# servo_1.net
KiCad netlist of a schematic drawn in EAGLE
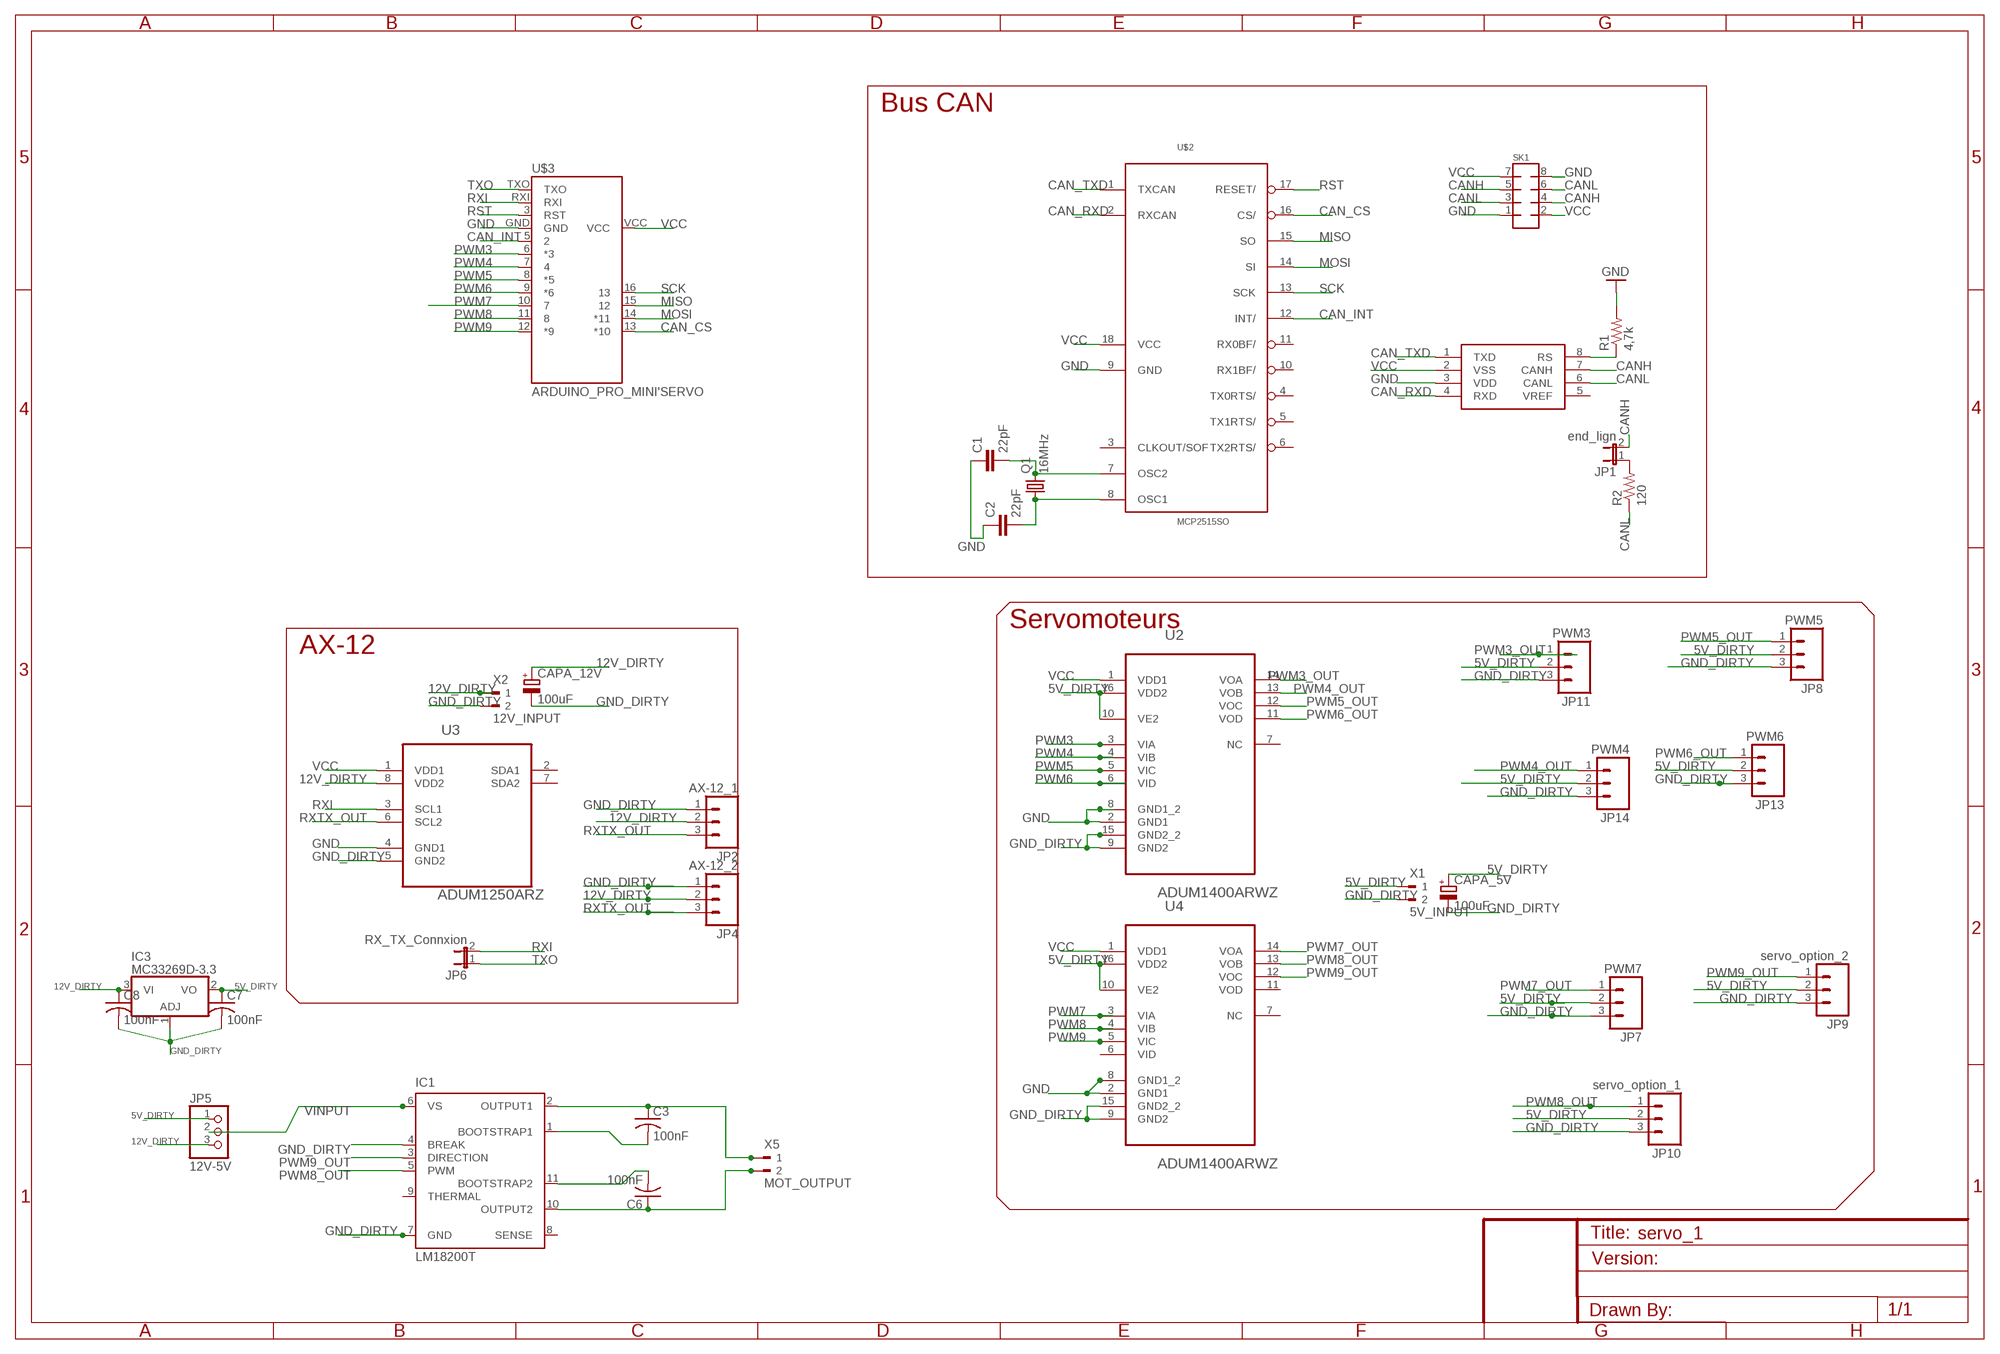
[diagram p0: schematic, sheet 1]

(export (version "E")
  (design (tool "Eeschema 10.0.6"))
  (components
    (comp (ref "C1")
      (value "22pF")
      (footprint "eagle-import:0805")
      (libsource (lib "eagle-import") (part "CAP0805"))
    )
    (comp (ref "C2")
      (value "22pF")
      (footprint "eagle-import:0805")
      (libsource (lib "eagle-import") (part "CAP0805"))
    )
    (comp (ref "C3")
      (value "100nF")
      (footprint "eagle-import:C0805")
      (libsource (lib "eagle-import") (part "C-USC0805"))
    )
    (comp (ref "C6")
      (value "100nF")
      (footprint "eagle-import:C0805")
      (libsource (lib "eagle-import") (part "C-USC0805"))
    )
    (comp (ref "C7")
      (value "100nF")
      (footprint "eagle-import:C0805")
      (libsource (lib "eagle-import") (part "C-USC0805"))
    )
    (comp (ref "C8")
      (value "100nF")
      (footprint "eagle-import:C0805")
      (libsource (lib "eagle-import") (part "C-USC0805"))
    )
    (comp (ref "CAPA_5V")
      (value "100uF")
      (footprint "eagle-import:E5-8,5")
      (libsource (lib "eagle-import") (part "CPOL-EUE5-8.5"))
    )
    (comp (ref "CAPA_12V")
      (value "100uF")
      (footprint "eagle-import:E5-8,5")
      (libsource (lib "eagle-import") (part "CPOL-EUE5-8.5"))
    )
    (comp (ref "IC1")
      (value "LM18200T")
      (footprint "eagle-import:TO-220-11")
      (libsource (lib "eagle-import") (part "LM18200T"))
    )
    (comp (ref "IC3")
      (value "MC33269D-3.3")
      (footprint "eagle-import:DPACK")
      (libsource (lib "eagle-import") (part "MC33269?D-3.3"))
    )
    (comp (ref "JP1")
      (value "end_lign")
      (footprint "eagle-import:1X02")
      (libsource (lib "eagle-import") (part "JUMPER-2PTH"))
    )
    (comp (ref "JP2")
      (value "AX-12_1")
      (footprint "eagle-import:MOLEX-1X3")
      (libsource (lib "eagle-import") (part "M03POLAR"))
    )
    (comp (ref "JP4")
      (value "AX-12_2")
      (footprint "eagle-import:MOLEX-1X3")
      (libsource (lib "eagle-import") (part "M03POLAR"))
    )
    (comp (ref "JP5")
      (value "12V-5V")
      (footprint "eagle-import:1X03")
      (libsource (lib "eagle-import") (part "PINHD-1X3"))
    )
    (comp (ref "JP6")
      (value "RX_TX_Connxion")
      (footprint "eagle-import:1X02")
      (libsource (lib "eagle-import") (part "JUMPER-2PTH"))
    )
    (comp (ref "JP7")
      (value "PWM7")
      (footprint "eagle-import:1X03")
      (libsource (lib "eagle-import") (part "M03PTH"))
    )
    (comp (ref "JP8")
      (value "PWM5")
      (footprint "eagle-import:1X03")
      (libsource (lib "eagle-import") (part "M03PTH"))
    )
    (comp (ref "JP9")
      (value "servo_option_2")
      (footprint "eagle-import:1X03")
      (libsource (lib "eagle-import") (part "M03PTH"))
    )
    (comp (ref "JP10")
      (value "servo_option_1")
      (footprint "eagle-import:1X03")
      (libsource (lib "eagle-import") (part "M03PTH"))
    )
    (comp (ref "JP11")
      (value "PWM3")
      (footprint "eagle-import:1X03")
      (libsource (lib "eagle-import") (part "M03PTH"))
    )
    (comp (ref "JP13")
      (value "PWM6")
      (footprint "eagle-import:1X03")
      (libsource (lib "eagle-import") (part "M03PTH"))
    )
    (comp (ref "JP14")
      (value "PWM4")
      (footprint "eagle-import:1X03")
      (libsource (lib "eagle-import") (part "M03PTH"))
    )
    (comp (ref "Q1")
      (value "16MHz")
      (footprint "eagle-import:HC49_S")
      (libsource (lib "eagle-import") (part "CRYSTALHC49S"))
    )
    (comp (ref "R1")
      (value "4,7k")
      (footprint "eagle-import:0805")
      (libsource (lib "eagle-import") (part "RESISTOR0805-RES"))
    )
    (comp (ref "R2")
      (value "120")
      (footprint "eagle-import:0805")
      (libsource (lib "eagle-import") (part "RESISTOR0805-RES"))
    )
    (comp (ref "SK1")
      (value "MMATCH-8-PTH")
      (footprint "eagle-import:AMP-215079-8")
      (libsource (lib "eagle-import") (part "MMATCH-8-PTH"))
    )
    (comp (ref "U$2")
      (value "MCP2515SO")
      (footprint "eagle-import:SO18L")
      (libsource (lib "eagle-import") (part "MCP2515SO"))
    )
    (comp (ref "U$3")
      (value "ARDUINO_PRO_MINI'SERVO")
      (footprint "eagle-import:ARDUINO_PRO_MINI")
      (libsource (lib "eagle-import") (part "ARDUINO_PRO_MINI'SERVO"))
    )
    (comp (ref "U1")
      (value "MCP2551")
      (footprint "eagle-import:SO08")
      (libsource (lib "eagle-import") (part "MCP2551"))
    )
    (comp (ref "U2")
      (value "ADUM1400ARWZ")
      (footprint "eagle-import:SOIC127P1032X265-16N")
      (libsource (lib "eagle-import") (part "ADUM1400ARWZ"))
    )
    (comp (ref "U3")
      (value "ADUM1250ARZ")
      (footprint "eagle-import:SOIC127P600X175-8N")
      (libsource (lib "eagle-import") (part "ADUM1250ARZ"))
    )
    (comp (ref "U4")
      (value "ADUM1400ARWZ")
      (footprint "eagle-import:SOIC127P1032X265-16N")
      (libsource (lib "eagle-import") (part "ADUM1400ARWZ"))
    )
    (comp (ref "X1")
      (value "5V_INPUT")
      (footprint "eagle-import:90-2")
      (libsource (lib "eagle-import") (part "90-2"))
    )
    (comp (ref "X2")
      (value "12V_INPUT")
      (footprint "eagle-import:90-2")
      (libsource (lib "eagle-import") (part "90-2"))
    )
    (comp (ref "X5")
      (value "MOT_OUTPUT")
      (footprint "eagle-import:90-2")
      (libsource (lib "eagle-import") (part "90-2"))
    )
  )
  (nets
    (net (code "1") (name "/5V_DIRTY") (class "Default")
      (node (ref "C7") (pin "1") (pinfunction "1_1") (pintype "passive"))
      (node (ref "CAPA_5V") (pin "+") (pinfunction "+_+") (pintype "passive"))
      (node (ref "IC3") (pin "2") (pinfunction "VO_2") (pintype "passive"))
      (node (ref "JP10") (pin "2") (pinfunction "2_2") (pintype "passive"))
      (node (ref "JP11") (pin "2") (pinfunction "2_2") (pintype "passive"))
      (node (ref "JP13") (pin "2") (pinfunction "2_2") (pintype "passive"))
      (node (ref "JP14") (pin "2") (pinfunction "2_2") (pintype "passive"))
      (node (ref "JP5") (pin "1") (pinfunction "1_1") (pintype "passive"))
      (node (ref "JP7") (pin "2") (pinfunction "2_2") (pintype "passive"))
      (node (ref "JP8") (pin "2") (pinfunction "2_2") (pintype "passive"))
      (node (ref "JP9") (pin "2") (pinfunction "2_2") (pintype "passive"))
      (node (ref "U2") (pin "10") (pinfunction "VE2_10") (pintype "input"))
      (node (ref "U2") (pin "16") (pinfunction "VDD2_16") (pintype "power_in"))
      (node (ref "U4") (pin "10") (pinfunction "VE2_10") (pintype "input"))
      (node (ref "U4") (pin "16") (pinfunction "VDD2_16") (pintype "power_in"))
      (node (ref "X1") (pin "1") (pinfunction "1_1") (pintype "passive"))
    )
    (net (code "2") (name "/12V_DIRTY") (class "Default")
      (node (ref "C8") (pin "1") (pinfunction "1_1") (pintype "passive"))
      (node (ref "CAPA_12V") (pin "+") (pinfunction "+_+") (pintype "passive"))
      (node (ref "IC3") (pin "3") (pinfunction "VI_3") (pintype "input"))
      (node (ref "JP2") (pin "2") (pinfunction "2_2") (pintype "passive"))
      (node (ref "JP4") (pin "2") (pinfunction "2_2") (pintype "passive"))
      (node (ref "JP5") (pin "3") (pinfunction "3_3") (pintype "passive"))
      (node (ref "U3") (pin "8") (pinfunction "VDD2_8") (pintype "power_in"))
      (node (ref "X2") (pin "1") (pinfunction "1_1") (pintype "passive"))
    )
    (net (code "3") (name "/CANH") (class "Default")
      (node (ref "JP1") (pin "2") (pinfunction "2_2") (pintype "passive"))
      (node (ref "SK1") (pin "4") (pinfunction "4_4") (pintype "bidirectional"))
      (node (ref "SK1") (pin "5") (pinfunction "5_5") (pintype "bidirectional"))
      (node (ref "U1") (pin "7") (pinfunction "CANH_7") (pintype "bidirectional"))
    )
    (net (code "4") (name "/CANL") (class "Default")
      (node (ref "R2") (pin "1") (pinfunction "1_1") (pintype "passive"))
      (node (ref "SK1") (pin "3") (pinfunction "3_3") (pintype "bidirectional"))
      (node (ref "SK1") (pin "6") (pinfunction "6_6") (pintype "bidirectional"))
      (node (ref "U1") (pin "6") (pinfunction "CANL_6") (pintype "bidirectional"))
    )
    (net (code "5") (name "/CAN_CS") (class "Default")
      (node (ref "U$2") (pin "16") (pinfunction "CS/_16") (pintype "input"))
      (node (ref "U$3") (pin "13") (pinfunction "*10_13") (pintype "bidirectional"))
    )
    (net (code "6") (name "/CAN_INT") (class "Default")
      (node (ref "U$2") (pin "12") (pinfunction "INT/_12") (pintype "output"))
      (node (ref "U$3") (pin "5") (pinfunction "2_5") (pintype "bidirectional"))
    )
    (net (code "7") (name "/CAN_RXD") (class "Default")
      (node (ref "U$2") (pin "2") (pinfunction "RXCAN_2") (pintype "input"))
      (node (ref "U1") (pin "4") (pinfunction "RXD_4") (pintype "bidirectional"))
    )
    (net (code "8") (name "/CAN_TXD") (class "Default")
      (node (ref "U$2") (pin "1") (pinfunction "TXCAN_1") (pintype "output"))
      (node (ref "U1") (pin "1") (pinfunction "TXD_1") (pintype "bidirectional"))
    )
    (net (code "9") (name "/GND_DIRTY") (class "Default")
      (node (ref "C7") (pin "2") (pinfunction "2_2") (pintype "passive"))
      (node (ref "C8") (pin "2") (pinfunction "2_2") (pintype "passive"))
      (node (ref "CAPA_12V") (pin "-") (pinfunction "-_-") (pintype "passive"))
      (node (ref "CAPA_5V") (pin "-") (pinfunction "-_-") (pintype "passive"))
      (node (ref "IC1") (pin "4") (pinfunction "BREAK_4") (pintype "input"))
      (node (ref "IC1") (pin "7") (pinfunction "GND_7") (pintype "power_in"))
      (node (ref "IC3") (pin "1") (pinfunction "ADJ_1") (pintype "input"))
      (node (ref "JP10") (pin "3") (pinfunction "3_3") (pintype "passive"))
      (node (ref "JP11") (pin "3") (pinfunction "3_3") (pintype "passive"))
      (node (ref "JP13") (pin "3") (pinfunction "3_3") (pintype "passive"))
      (node (ref "JP14") (pin "3") (pinfunction "3_3") (pintype "passive"))
      (node (ref "JP2") (pin "1") (pinfunction "1_1") (pintype "passive"))
      (node (ref "JP4") (pin "1") (pinfunction "1_1") (pintype "passive"))
      (node (ref "JP7") (pin "3") (pinfunction "3_3") (pintype "passive"))
      (node (ref "JP8") (pin "3") (pinfunction "3_3") (pintype "passive"))
      (node (ref "JP9") (pin "3") (pinfunction "3_3") (pintype "passive"))
      (node (ref "U2") (pin "15") (pinfunction "GND2_2_15") (pintype "passive"))
      (node (ref "U2") (pin "9") (pinfunction "GND2_9") (pintype "passive"))
      (node (ref "U3") (pin "5") (pinfunction "GND2_5") (pintype "passive"))
      (node (ref "U4") (pin "15") (pinfunction "GND2_2_15") (pintype "passive"))
      (node (ref "U4") (pin "9") (pinfunction "GND2_9") (pintype "passive"))
      (node (ref "X1") (pin "2") (pinfunction "2_2") (pintype "passive"))
      (node (ref "X2") (pin "2") (pinfunction "2_2") (pintype "passive"))
    )
    (net (code "10") (name "/MISO") (class "Default")
      (node (ref "U$2") (pin "15") (pinfunction "SO_15") (pintype "output"))
      (node (ref "U$3") (pin "15") (pinfunction "12_15") (pintype "bidirectional"))
    )
    (net (code "11") (name "/MOSI") (class "Default")
      (node (ref "U$2") (pin "14") (pinfunction "SI_14") (pintype "input"))
      (node (ref "U$3") (pin "14") (pinfunction "*11_14") (pintype "bidirectional"))
    )
    (net (code "12") (name "/PWM3") (class "Default")
      (node (ref "U$3") (pin "6") (pinfunction "*3_6") (pintype "bidirectional"))
      (node (ref "U2") (pin "3") (pinfunction "VIA_3") (pintype "input"))
    )
    (net (code "13") (name "/PWM3_OUT") (class "Default")
      (node (ref "JP11") (pin "1") (pinfunction "1_1") (pintype "passive"))
      (node (ref "U2") (pin "14") (pinfunction "VOA_14") (pintype "output"))
    )
    (net (code "14") (name "/PWM4") (class "Default")
      (node (ref "U$3") (pin "7") (pinfunction "4_7") (pintype "bidirectional"))
      (node (ref "U2") (pin "4") (pinfunction "VIB_4") (pintype "input"))
    )
    (net (code "15") (name "/PWM4_OUT") (class "Default")
      (node (ref "JP14") (pin "1") (pinfunction "1_1") (pintype "passive"))
      (node (ref "U2") (pin "13") (pinfunction "VOB_13") (pintype "output"))
    )
    (net (code "16") (name "/PWM5") (class "Default")
      (node (ref "U$3") (pin "8") (pinfunction "*5_8") (pintype "bidirectional"))
      (node (ref "U2") (pin "5") (pinfunction "VIC_5") (pintype "input"))
    )
    (net (code "17") (name "/PWM5_OUT") (class "Default")
      (node (ref "JP8") (pin "1") (pinfunction "1_1") (pintype "passive"))
      (node (ref "U2") (pin "12") (pinfunction "VOC_12") (pintype "output"))
    )
    (net (code "18") (name "/PWM6") (class "Default")
      (node (ref "U$3") (pin "9") (pinfunction "*6_9") (pintype "bidirectional"))
      (node (ref "U2") (pin "6") (pinfunction "VID_6") (pintype "input"))
    )
    (net (code "19") (name "/PWM6_OUT") (class "Default")
      (node (ref "JP13") (pin "1") (pinfunction "1_1") (pintype "passive"))
      (node (ref "U2") (pin "11") (pinfunction "VOD_11") (pintype "output"))
    )
    (net (code "20") (name "/PWM7") (class "Default")
      (node (ref "U$3") (pin "10") (pinfunction "7_10") (pintype "bidirectional"))
      (node (ref "U4") (pin "3") (pinfunction "VIA_3") (pintype "input"))
    )
    (net (code "21") (name "/PWM7_OUT") (class "Default")
      (node (ref "JP7") (pin "1") (pinfunction "1_1") (pintype "passive"))
      (node (ref "U4") (pin "14") (pinfunction "VOA_14") (pintype "output"))
    )
    (net (code "22") (name "/PWM8") (class "Default")
      (node (ref "U$3") (pin "11") (pinfunction "8_11") (pintype "bidirectional"))
      (node (ref "U4") (pin "4") (pinfunction "VIB_4") (pintype "input"))
    )
    (net (code "23") (name "/PWM8_OUT") (class "Default")
      (node (ref "IC1") (pin "5") (pinfunction "PWM_5") (pintype "input"))
      (node (ref "JP10") (pin "1") (pinfunction "1_1") (pintype "passive"))
      (node (ref "U4") (pin "13") (pinfunction "VOB_13") (pintype "output"))
    )
    (net (code "24") (name "/PWM9") (class "Default")
      (node (ref "U$3") (pin "12") (pinfunction "*9_12") (pintype "bidirectional"))
      (node (ref "U4") (pin "5") (pinfunction "VIC_5") (pintype "input"))
    )
    (net (code "25") (name "/PWM9_OUT") (class "Default")
      (node (ref "IC1") (pin "3") (pinfunction "DIRECTION_3") (pintype "input"))
      (node (ref "JP9") (pin "1") (pinfunction "1_1") (pintype "passive"))
      (node (ref "U4") (pin "12") (pinfunction "VOC_12") (pintype "output"))
    )
    (net (code "26") (name "/RST") (class "Default")
      (node (ref "U$2") (pin "17") (pinfunction "RESET/_17") (pintype "input"))
      (node (ref "U$3") (pin "3") (pinfunction "RST_3") (pintype "bidirectional"))
    )
    (net (code "27") (name "/RXI") (class "Default")
      (node (ref "JP6") (pin "2") (pinfunction "2_2") (pintype "passive"))
      (node (ref "U$3") (pin "RXI") (pinfunction "RXI_RXI") (pintype "bidirectional"))
      (node (ref "U3") (pin "3") (pinfunction "SCL1_3") (pintype "input"))
    )
    (net (code "28") (name "/RXTX_OUT") (class "Default")
      (node (ref "JP2") (pin "3") (pinfunction "3_3") (pintype "passive"))
      (node (ref "JP4") (pin "3") (pinfunction "3_3") (pintype "passive"))
      (node (ref "U3") (pin "6") (pinfunction "SCL2_6") (pintype "input"))
    )
    (net (code "29") (name "/SCK") (class "Default")
      (node (ref "U$2") (pin "13") (pinfunction "SCK_13") (pintype "input"))
      (node (ref "U$3") (pin "16") (pinfunction "13_16") (pintype "bidirectional"))
    )
    (net (code "30") (name "/TXO") (class "Default")
      (node (ref "JP6") (pin "1") (pinfunction "1_1") (pintype "passive"))
      (node (ref "U$3") (pin "TXO") (pinfunction "TXO_TXO") (pintype "bidirectional"))
    )
    (net (code "31") (name "/VCC") (class "Default")
      (node (ref "SK1") (pin "2") (pinfunction "2_2") (pintype "bidirectional"))
      (node (ref "SK1") (pin "7") (pinfunction "7_7") (pintype "bidirectional"))
      (node (ref "U$2") (pin "18") (pinfunction "VCC_18") (pintype "power_in"))
      (node (ref "U$3") (pin "VCC") (pinfunction "VCC_VCC") (pintype "bidirectional"))
      (node (ref "U1") (pin "2") (pinfunction "VSS_2") (pintype "bidirectional"))
      (node (ref "U2") (pin "1") (pinfunction "VDD1_1") (pintype "power_in"))
      (node (ref "U3") (pin "1") (pinfunction "VDD1_1") (pintype "power_in"))
      (node (ref "U4") (pin "1") (pinfunction "VDD1_1") (pintype "power_in"))
    )
    (net (code "32") (name "/VINPUT") (class "Default")
      (node (ref "IC1") (pin "6") (pinfunction "VS_6") (pintype "power_in"))
      (node (ref "JP5") (pin "2") (pinfunction "2_2") (pintype "passive"))
    )
    (net (code "33") (name "GND") (class "Default")
      (node (ref "C1") (pin "1") (pinfunction "1_1") (pintype "passive"))
      (node (ref "C2") (pin "1") (pinfunction "1_1") (pintype "passive"))
      (node (ref "R1") (pin "2") (pinfunction "2_2") (pintype "passive"))
      (node (ref "SK1") (pin "1") (pinfunction "1_1") (pintype "bidirectional"))
      (node (ref "SK1") (pin "8") (pinfunction "8_8") (pintype "bidirectional"))
      (node (ref "U$2") (pin "9") (pinfunction "GND_9") (pintype "power_in"))
      (node (ref "U$3") (pin "GND") (pinfunction "GND_GND") (pintype "bidirectional"))
      (node (ref "U1") (pin "3") (pinfunction "VDD_3") (pintype "bidirectional"))
      (node (ref "U2") (pin "2") (pinfunction "GND1_2") (pintype "passive"))
      (node (ref "U2") (pin "8") (pinfunction "GND1_2_8") (pintype "passive"))
      (node (ref "U3") (pin "4") (pinfunction "GND1_4") (pintype "passive"))
      (node (ref "U4") (pin "2") (pinfunction "GND1_2") (pintype "passive"))
      (node (ref "U4") (pin "8") (pinfunction "GND1_2_8") (pintype "passive"))
    )
    (net (code "34") (name "Net-(IC1-BOOTSTRAP1)") (class "Default")
      (node (ref "C3") (pin "2") (pinfunction "2_2") (pintype "passive"))
      (node (ref "IC1") (pin "1") (pinfunction "BOOTSTRAP1_1") (pintype "input"))
    )
    (net (code "35") (name "Net-(IC1-BOOTSTRAP2)") (class "Default")
      (node (ref "C6") (pin "2") (pinfunction "2_2") (pintype "passive"))
      (node (ref "IC1") (pin "11") (pinfunction "BOOTSTRAP2_11") (pintype "input"))
    )
    (net (code "36") (name "Net-(IC1-OUTPUT1)") (class "Default")
      (node (ref "C3") (pin "1") (pinfunction "1_1") (pintype "passive"))
      (node (ref "IC1") (pin "2") (pinfunction "OUTPUT1_2") (pintype "output"))
      (node (ref "X5") (pin "1") (pinfunction "1_1") (pintype "passive"))
    )
    (net (code "37") (name "Net-(IC1-OUTPUT2)") (class "Default")
      (node (ref "C6") (pin "1") (pinfunction "1_1") (pintype "passive"))
      (node (ref "IC1") (pin "10") (pinfunction "OUTPUT2_10") (pintype "output"))
      (node (ref "X5") (pin "2") (pinfunction "2_2") (pintype "passive"))
    )
    (net (code "38") (name "Net-(JP1-Pad1)") (class "Default")
      (node (ref "JP1") (pin "1") (pinfunction "1_1") (pintype "passive"))
      (node (ref "R2") (pin "2") (pinfunction "2_2") (pintype "passive"))
    )
    (net (code "39") (name "Net-(U$2-OSC1)") (class "Default")
      (node (ref "C2") (pin "2") (pinfunction "2_2") (pintype "passive"))
      (node (ref "Q1") (pin "1") (pinfunction "1_1") (pintype "passive"))
      (node (ref "U$2") (pin "8") (pinfunction "OSC1_8") (pintype "bidirectional"))
    )
    (net (code "40") (name "Net-(U$2-OSC2)") (class "Default")
      (node (ref "C1") (pin "2") (pinfunction "2_2") (pintype "passive"))
      (node (ref "Q1") (pin "2") (pinfunction "2_2") (pintype "passive"))
      (node (ref "U$2") (pin "7") (pinfunction "OSC2_7") (pintype "bidirectional"))
    )
    (net (code "41") (name "Net-(U1-RS)") (class "Default")
      (node (ref "R1") (pin "1") (pinfunction "1_1") (pintype "passive"))
      (node (ref "U1") (pin "8") (pinfunction "RS_8") (pintype "bidirectional"))
    )
    (net (code "42") (name "unconnected-(IC1-SENSE-Pad8)") (class "Default")
      (node (ref "IC1") (pin "8") (pinfunction "SENSE_8") (pintype "output"))
    )
    (net (code "43") (name "unconnected-(IC1-THERMAL-Pad9)") (class "Default")
      (node (ref "IC1") (pin "9") (pinfunction "THERMAL_9") (pintype "output"))
    )
    (net (code "44") (name "unconnected-(U$2-CLKOUT{slash}SOF-Pad3)") (class "Default")
      (node (ref "U$2") (pin "3") (pinfunction "CLKOUT/SOF_3") (pintype "bidirectional"))
    )
    (net (code "45") (name "unconnected-(U$2-RX0BF{slash}-Pad11)") (class "Default")
      (node (ref "U$2") (pin "11") (pinfunction "RX0BF/_11") (pintype "bidirectional"))
    )
    (net (code "46") (name "unconnected-(U$2-RX1BF{slash}-Pad10)") (class "Default")
      (node (ref "U$2") (pin "10") (pinfunction "RX1BF/_10") (pintype "bidirectional"))
    )
    (net (code "47") (name "unconnected-(U$2-TX0RTS{slash}-Pad4)") (class "Default")
      (node (ref "U$2") (pin "4") (pinfunction "TX0RTS/_4") (pintype "bidirectional"))
    )
    (net (code "48") (name "unconnected-(U$2-TX1RTS{slash}-Pad5)") (class "Default")
      (node (ref "U$2") (pin "5") (pinfunction "TX1RTS/_5") (pintype "bidirectional"))
    )
    (net (code "49") (name "unconnected-(U$2-TX2RTS{slash}-Pad6)") (class "Default")
      (node (ref "U$2") (pin "6") (pinfunction "TX2RTS/_6") (pintype "bidirectional"))
    )
    (net (code "50") (name "unconnected-(U1-VREF-Pad5)") (class "Default")
      (node (ref "U1") (pin "5") (pinfunction "VREF_5") (pintype "bidirectional"))
    )
    (net (code "51") (name "unconnected-(U2-NC-Pad7)") (class "Default")
      (node (ref "U2") (pin "7") (pinfunction "NC_7") (pintype "no_connect"))
    )
    (net (code "52") (name "unconnected-(U3-SDA1-Pad2)") (class "Default")
      (node (ref "U3") (pin "2") (pinfunction "SDA1_2") (pintype "bidirectional"))
    )
    (net (code "53") (name "unconnected-(U3-SDA2-Pad7)") (class "Default")
      (node (ref "U3") (pin "7") (pinfunction "SDA2_7") (pintype "bidirectional"))
    )
    (net (code "54") (name "unconnected-(U4-NC-Pad7)") (class "Default")
      (node (ref "U4") (pin "7") (pinfunction "NC_7") (pintype "no_connect"))
    )
    (net (code "55") (name "unconnected-(U4-VID-Pad6)") (class "Default")
      (node (ref "U4") (pin "6") (pinfunction "VID_6") (pintype "input"))
    )
    (net (code "56") (name "unconnected-(U4-VOD-Pad11)") (class "Default")
      (node (ref "U4") (pin "11") (pinfunction "VOD_11") (pintype "output"))
    )
  )
)
